# Sheet1.net
KiCad netlist of a schematic drawn in Altium Designer
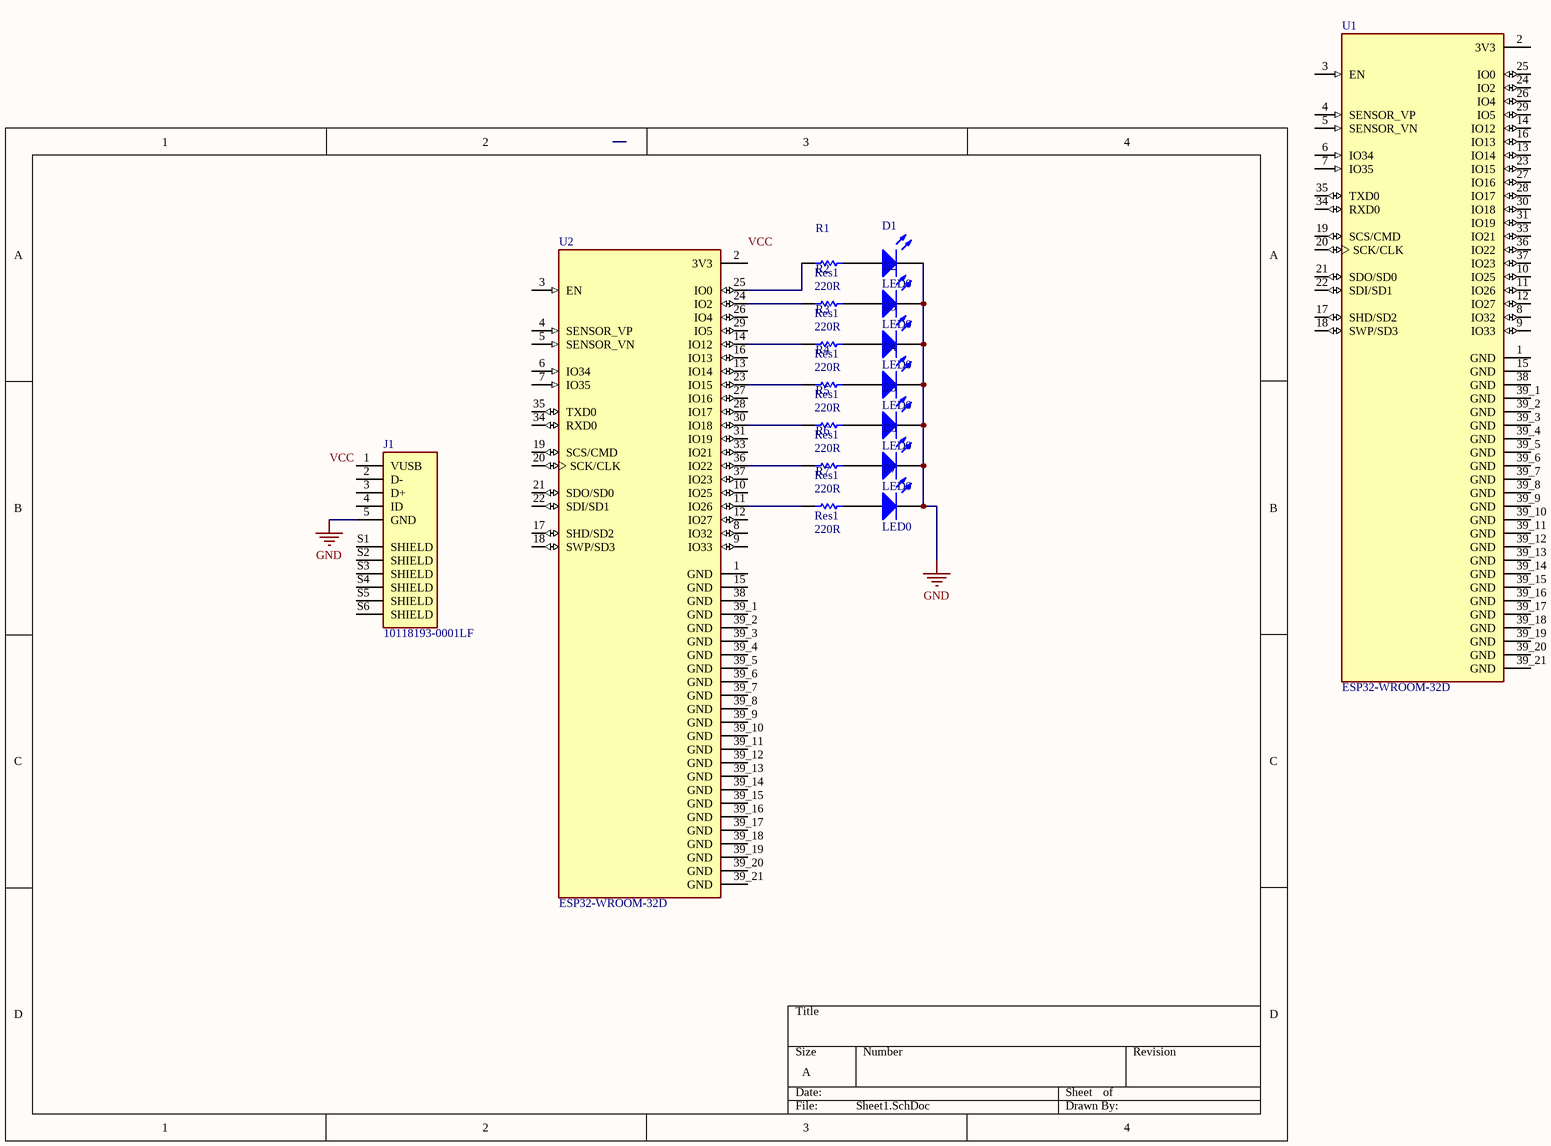
[diagram p0: Sheet1.SchDoc]

(export (version "E")
  (design (tool "Eeschema 10.0.6"))
  (components
    (comp (ref "D1")
      (value "LED0")
      (footprint "LED-0")
      (description "Typical INFRARED GaAs LED")
      (fields (field (name "PUBLISHER") "Altium Limited"))
      (libsource (lib "Miscellaneous Devices") (part "LED0"))
    )
    (comp (ref "D2")
      (value "LED0")
      (footprint "LED-0")
      (description "Typical INFRARED GaAs LED")
      (fields (field (name "PUBLISHER") "Altium Limited"))
      (libsource (lib "Miscellaneous Devices") (part "LED0"))
    )
    (comp (ref "D3")
      (value "LED0")
      (footprint "LED-0")
      (description "Typical INFRARED GaAs LED")
      (fields (field (name "PUBLISHER") "Altium Limited"))
      (libsource (lib "Miscellaneous Devices") (part "LED0"))
    )
    (comp (ref "D4")
      (value "LED0")
      (footprint "LED-0")
      (description "Typical INFRARED GaAs LED")
      (fields (field (name "PUBLISHER") "Altium Limited"))
      (libsource (lib "Miscellaneous Devices") (part "LED0"))
    )
    (comp (ref "D5")
      (value "LED0")
      (footprint "LED-0")
      (description "Typical INFRARED GaAs LED")
      (fields (field (name "PUBLISHER") "Altium Limited"))
      (libsource (lib "Miscellaneous Devices") (part "LED0"))
    )
    (comp (ref "D6")
      (value "LED0")
      (footprint "LED-0")
      (description "Typical INFRARED GaAs LED")
      (fields (field (name "PUBLISHER") "Altium Limited"))
      (libsource (lib "Miscellaneous Devices") (part "LED0"))
    )
    (comp (ref "D7")
      (value "LED0")
      (footprint "LED-0")
      (description "Typical INFRARED GaAs LED")
      (fields (field (name "PUBLISHER") "Altium Limited"))
      (libsource (lib "Miscellaneous Devices") (part "LED0"))
    )
    (comp (ref "J1")
      (value "10118193-0001LF")
      (footprint "AMPHENOL_10118193-0001LF")
      (description "Micro USB 2.0, Input Output Connectors, B TYPE RECEPTACLE")
      (fields (field (name "MF") "Amphenol ICC"))
      (libsource (lib "10118193-0001LF") (part "10118193-0001LF"))
    )
    (comp (ref "R1")
      (value "Res1")
      (footprint "AXIAL-0.3")
      (description "Resistor")
      (fields (field (name "ALTIUM_VALUE") "220R") (field (name "PUBLISHER") "Altium Limited"))
      (libsource (lib "Miscellaneous Devices") (part "Res1"))
    )
    (comp (ref "R2")
      (value "Res1")
      (footprint "AXIAL-0.3")
      (description "Resistor")
      (fields (field (name "ALTIUM_VALUE") "220R") (field (name "PUBLISHER") "Altium Limited"))
      (libsource (lib "Miscellaneous Devices") (part "Res1"))
    )
    (comp (ref "R3")
      (value "Res1")
      (footprint "AXIAL-0.3")
      (description "Resistor")
      (fields (field (name "ALTIUM_VALUE") "220R") (field (name "PUBLISHER") "Altium Limited"))
      (libsource (lib "Miscellaneous Devices") (part "Res1"))
    )
    (comp (ref "R4")
      (value "Res1")
      (footprint "AXIAL-0.3")
      (description "Resistor")
      (fields (field (name "ALTIUM_VALUE") "220R") (field (name "PUBLISHER") "Altium Limited"))
      (libsource (lib "Miscellaneous Devices") (part "Res1"))
    )
    (comp (ref "R5")
      (value "Res1")
      (footprint "AXIAL-0.3")
      (description "Resistor")
      (fields (field (name "ALTIUM_VALUE") "220R") (field (name "PUBLISHER") "Altium Limited"))
      (libsource (lib "Miscellaneous Devices") (part "Res1"))
    )
    (comp (ref "R6")
      (value "Res1")
      (footprint "AXIAL-0.3")
      (description "Resistor")
      (fields (field (name "ALTIUM_VALUE") "220R") (field (name "PUBLISHER") "Altium Limited"))
      (libsource (lib "Miscellaneous Devices") (part "Res1"))
    )
    (comp (ref "R7")
      (value "Res1")
      (footprint "AXIAL-0.3")
      (description "Resistor")
      (fields (field (name "ALTIUM_VALUE") "220R") (field (name "PUBLISHER") "Altium Limited"))
      (libsource (lib "Miscellaneous Devices") (part "Res1"))
    )
    (comp (ref "U1")
      (value "ESP32-WROOM-32D")
      (footprint "MODULE_ESP32-WROOM-32D")
      (fields (field (name "MF") "Espressif Systems"))
      (libsource (lib "ESP32-WROOM-32D") (part "ESP32-WROOM-32D"))
    )
    (comp (ref "U2")
      (value "ESP32-WROOM-32D")
      (footprint "MODULE_ESP32-WROOM-32D")
      (fields (field (name "MF") "Espressif Systems"))
      (libsource (lib "ESP32-WROOM-32D") (part "ESP32-WROOM-32D"))
    )
  )
  (nets
    (net (code "2") (name "GND") (class "Default")
      (node (ref "D1") (pin "2") (pinfunction "K_2") (pintype "passive"))
      (node (ref "D2") (pin "2") (pinfunction "K_2") (pintype "passive"))
      (node (ref "D3") (pin "2") (pinfunction "K_2") (pintype "passive"))
      (node (ref "D4") (pin "2") (pinfunction "K_2") (pintype "passive"))
      (node (ref "D5") (pin "2") (pinfunction "K_2") (pintype "passive"))
      (node (ref "D6") (pin "2") (pinfunction "K_2") (pintype "passive"))
      (node (ref "D7") (pin "2") (pinfunction "K_2") (pintype "passive"))
      (node (ref "J1") (pin "5") (pinfunction "GND_5") (pintype "passive"))
    )
    (net (code "3") (name "Net-(D1-A)") (class "Default")
      (node (ref "D1") (pin "1") (pinfunction "A_1") (pintype "passive"))
      (node (ref "R1") (pin "2") (pinfunction "2_2") (pintype "passive"))
    )
    (net (code "4") (name "Net-(D2-A)") (class "Default")
      (node (ref "D2") (pin "1") (pinfunction "A_1") (pintype "passive"))
      (node (ref "R2") (pin "2") (pinfunction "2_2") (pintype "passive"))
    )
    (net (code "5") (name "Net-(D3-A)") (class "Default")
      (node (ref "D3") (pin "1") (pinfunction "A_1") (pintype "passive"))
      (node (ref "R3") (pin "2") (pinfunction "2_2") (pintype "passive"))
    )
    (net (code "6") (name "Net-(D4-A)") (class "Default")
      (node (ref "D4") (pin "1") (pinfunction "A_1") (pintype "passive"))
      (node (ref "R4") (pin "2") (pinfunction "2_2") (pintype "passive"))
    )
    (net (code "7") (name "Net-(D5-A)") (class "Default")
      (node (ref "D5") (pin "1") (pinfunction "A_1") (pintype "passive"))
      (node (ref "R5") (pin "2") (pinfunction "2_2") (pintype "passive"))
    )
    (net (code "8") (name "Net-(D6-A)") (class "Default")
      (node (ref "D6") (pin "1") (pinfunction "A_1") (pintype "passive"))
      (node (ref "R6") (pin "2") (pinfunction "2_2") (pintype "passive"))
    )
    (net (code "9") (name "Net-(D7-A)") (class "Default")
      (node (ref "D7") (pin "1") (pinfunction "A_1") (pintype "passive"))
      (node (ref "R7") (pin "2") (pinfunction "2_2") (pintype "passive"))
    )
    (net (code "10") (name "Net-(U2-IO0)") (class "Default")
      (node (ref "R1") (pin "1") (pinfunction "1_1") (pintype "passive"))
      (node (ref "U2") (pin "25") (pinfunction "IO0_25") (pintype "bidirectional"))
    )
    (net (code "11") (name "Net-(U2-IO2)") (class "Default")
      (node (ref "R2") (pin "1") (pinfunction "1_1") (pintype "passive"))
      (node (ref "U2") (pin "24") (pinfunction "IO2_24") (pintype "bidirectional"))
    )
    (net (code "12") (name "Net-(U2-IO12)") (class "Default")
      (node (ref "R3") (pin "1") (pinfunction "1_1") (pintype "passive"))
      (node (ref "U2") (pin "14") (pinfunction "IO12_14") (pintype "bidirectional"))
    )
    (net (code "13") (name "Net-(U2-IO15)") (class "Default")
      (node (ref "R4") (pin "1") (pinfunction "1_1") (pintype "passive"))
      (node (ref "U2") (pin "23") (pinfunction "IO15_23") (pintype "bidirectional"))
    )
    (net (code "14") (name "Net-(U2-IO18)") (class "Default")
      (node (ref "R5") (pin "1") (pinfunction "1_1") (pintype "passive"))
      (node (ref "U2") (pin "30") (pinfunction "IO18_30") (pintype "bidirectional"))
    )
    (net (code "15") (name "Net-(U2-IO22)") (class "Default")
      (node (ref "R6") (pin "1") (pinfunction "1_1") (pintype "passive"))
      (node (ref "U2") (pin "36") (pinfunction "IO22_36") (pintype "bidirectional"))
    )
    (net (code "16") (name "Net-(U2-IO26)") (class "Default")
      (node (ref "R7") (pin "1") (pinfunction "1_1") (pintype "passive"))
      (node (ref "U2") (pin "11") (pinfunction "IO26_11") (pintype "bidirectional"))
    )
    (net (code "17") (name "unconnected-(J1-D+-Pad3)") (class "Default")
      (node (ref "J1") (pin "3") (pinfunction "D+_3") (pintype "passive"))
    )
    (net (code "18") (name "unconnected-(J1-D--Pad2)") (class "Default")
      (node (ref "J1") (pin "2") (pinfunction "D-_2") (pintype "passive"))
    )
    (net (code "19") (name "unconnected-(J1-ID-Pad4)") (class "Default")
      (node (ref "J1") (pin "4") (pinfunction "ID_4") (pintype "passive"))
    )
    (net (code "20") (name "unconnected-(J1-SHIELD-PadS1)") (class "Default")
      (node (ref "J1") (pin "S1") (pinfunction "SHIELD_S1") (pintype "passive"))
    )
    (net (code "21") (name "unconnected-(J1-SHIELD-PadS2)") (class "Default")
      (node (ref "J1") (pin "S2") (pinfunction "SHIELD_S2") (pintype "passive"))
    )
    (net (code "22") (name "unconnected-(J1-SHIELD-PadS3)") (class "Default")
      (node (ref "J1") (pin "S3") (pinfunction "SHIELD_S3") (pintype "passive"))
    )
    (net (code "23") (name "unconnected-(J1-SHIELD-PadS4)") (class "Default")
      (node (ref "J1") (pin "S4") (pinfunction "SHIELD_S4") (pintype "passive"))
    )
    (net (code "24") (name "unconnected-(J1-SHIELD-PadS5)") (class "Default")
      (node (ref "J1") (pin "S5") (pinfunction "SHIELD_S5") (pintype "passive"))
    )
    (net (code "25") (name "unconnected-(J1-SHIELD-PadS6)") (class "Default")
      (node (ref "J1") (pin "S6") (pinfunction "SHIELD_S6") (pintype "passive"))
    )
    (net (code "26") (name "unconnected-(J1-VUSB-Pad1)") (class "Default")
      (node (ref "J1") (pin "1") (pinfunction "VUSB_1") (pintype "passive"))
    )
    (net (code "27") (name "unconnected-(U1-3V3-Pad2)") (class "Default")
      (node (ref "U1") (pin "2") (pinfunction "3V3_2") (pintype "power_in"))
    )
    (net (code "28") (name "unconnected-(U1-EN-Pad3)") (class "Default")
      (node (ref "U1") (pin "3") (pinfunction "EN_3") (pintype "input"))
    )
    (net (code "29") (name "unconnected-(U1-GND-Pad1)") (class "Default")
      (node (ref "U1") (pin "1") (pinfunction "GND_1") (pintype "power_in"))
    )
    (net (code "30") (name "unconnected-(U1-GND-Pad15)") (class "Default")
      (node (ref "U1") (pin "15") (pinfunction "GND_15") (pintype "power_in"))
    )
    (net (code "31") (name "unconnected-(U1-GND-Pad38)") (class "Default")
      (node (ref "U1") (pin "38") (pinfunction "GND_38") (pintype "power_in"))
    )
    (net (code "32") (name "unconnected-(U1-GND-Pad39_1)") (class "Default")
      (node (ref "U1") (pin "39_1") (pinfunction "GND_39_1") (pintype "power_in"))
    )
    (net (code "33") (name "unconnected-(U1-GND-Pad39_2)") (class "Default")
      (node (ref "U1") (pin "39_2") (pinfunction "GND_39_2") (pintype "power_in"))
    )
    (net (code "34") (name "unconnected-(U1-GND-Pad39_3)") (class "Default")
      (node (ref "U1") (pin "39_3") (pinfunction "GND_39_3") (pintype "power_in"))
    )
    (net (code "35") (name "unconnected-(U1-GND-Pad39_4)") (class "Default")
      (node (ref "U1") (pin "39_4") (pinfunction "GND_39_4") (pintype "power_in"))
    )
    (net (code "36") (name "unconnected-(U1-GND-Pad39_5)") (class "Default")
      (node (ref "U1") (pin "39_5") (pinfunction "GND_39_5") (pintype "power_in"))
    )
    (net (code "37") (name "unconnected-(U1-GND-Pad39_6)") (class "Default")
      (node (ref "U1") (pin "39_6") (pinfunction "GND_39_6") (pintype "power_in"))
    )
    (net (code "38") (name "unconnected-(U1-GND-Pad39_7)") (class "Default")
      (node (ref "U1") (pin "39_7") (pinfunction "GND_39_7") (pintype "power_in"))
    )
    (net (code "39") (name "unconnected-(U1-GND-Pad39_8)") (class "Default")
      (node (ref "U1") (pin "39_8") (pinfunction "GND_39_8") (pintype "power_in"))
    )
    (net (code "40") (name "unconnected-(U1-GND-Pad39_9)") (class "Default")
      (node (ref "U1") (pin "39_9") (pinfunction "GND_39_9") (pintype "power_in"))
    )
    (net (code "41") (name "unconnected-(U1-GND-Pad39_10)") (class "Default")
      (node (ref "U1") (pin "39_10") (pinfunction "GND_39_10") (pintype "power_in"))
    )
    (net (code "42") (name "unconnected-(U1-GND-Pad39_11)") (class "Default")
      (node (ref "U1") (pin "39_11") (pinfunction "GND_39_11") (pintype "power_in"))
    )
    (net (code "43") (name "unconnected-(U1-GND-Pad39_12)") (class "Default")
      (node (ref "U1") (pin "39_12") (pinfunction "GND_39_12") (pintype "power_in"))
    )
    (net (code "44") (name "unconnected-(U1-GND-Pad39_13)") (class "Default")
      (node (ref "U1") (pin "39_13") (pinfunction "GND_39_13") (pintype "power_in"))
    )
    (net (code "45") (name "unconnected-(U1-GND-Pad39_14)") (class "Default")
      (node (ref "U1") (pin "39_14") (pinfunction "GND_39_14") (pintype "power_in"))
    )
    (net (code "46") (name "unconnected-(U1-GND-Pad39_15)") (class "Default")
      (node (ref "U1") (pin "39_15") (pinfunction "GND_39_15") (pintype "power_in"))
    )
    (net (code "47") (name "unconnected-(U1-GND-Pad39_16)") (class "Default")
      (node (ref "U1") (pin "39_16") (pinfunction "GND_39_16") (pintype "power_in"))
    )
    (net (code "48") (name "unconnected-(U1-GND-Pad39_17)") (class "Default")
      (node (ref "U1") (pin "39_17") (pinfunction "GND_39_17") (pintype "power_in"))
    )
    (net (code "49") (name "unconnected-(U1-GND-Pad39_18)") (class "Default")
      (node (ref "U1") (pin "39_18") (pinfunction "GND_39_18") (pintype "power_in"))
    )
    (net (code "50") (name "unconnected-(U1-GND-Pad39_19)") (class "Default")
      (node (ref "U1") (pin "39_19") (pinfunction "GND_39_19") (pintype "power_in"))
    )
    (net (code "51") (name "unconnected-(U1-GND-Pad39_20)") (class "Default")
      (node (ref "U1") (pin "39_20") (pinfunction "GND_39_20") (pintype "power_in"))
    )
    (net (code "52") (name "unconnected-(U1-GND-Pad39_21)") (class "Default")
      (node (ref "U1") (pin "39_21") (pinfunction "GND_39_21") (pintype "power_in"))
    )
    (net (code "53") (name "unconnected-(U1-IO0-Pad25)") (class "Default")
      (node (ref "U1") (pin "25") (pinfunction "IO0_25") (pintype "bidirectional"))
    )
    (net (code "54") (name "unconnected-(U1-IO2-Pad24)") (class "Default")
      (node (ref "U1") (pin "24") (pinfunction "IO2_24") (pintype "bidirectional"))
    )
    (net (code "55") (name "unconnected-(U1-IO4-Pad26)") (class "Default")
      (node (ref "U1") (pin "26") (pinfunction "IO4_26") (pintype "bidirectional"))
    )
    (net (code "56") (name "unconnected-(U1-IO5-Pad29)") (class "Default")
      (node (ref "U1") (pin "29") (pinfunction "IO5_29") (pintype "bidirectional"))
    )
    (net (code "57") (name "unconnected-(U1-IO12-Pad14)") (class "Default")
      (node (ref "U1") (pin "14") (pinfunction "IO12_14") (pintype "bidirectional"))
    )
    (net (code "58") (name "unconnected-(U1-IO13-Pad16)") (class "Default")
      (node (ref "U1") (pin "16") (pinfunction "IO13_16") (pintype "bidirectional"))
    )
    (net (code "59") (name "unconnected-(U1-IO14-Pad13)") (class "Default")
      (node (ref "U1") (pin "13") (pinfunction "IO14_13") (pintype "bidirectional"))
    )
    (net (code "60") (name "unconnected-(U1-IO15-Pad23)") (class "Default")
      (node (ref "U1") (pin "23") (pinfunction "IO15_23") (pintype "bidirectional"))
    )
    (net (code "61") (name "unconnected-(U1-IO16-Pad27)") (class "Default")
      (node (ref "U1") (pin "27") (pinfunction "IO16_27") (pintype "bidirectional"))
    )
    (net (code "62") (name "unconnected-(U1-IO17-Pad28)") (class "Default")
      (node (ref "U1") (pin "28") (pinfunction "IO17_28") (pintype "bidirectional"))
    )
    (net (code "63") (name "unconnected-(U1-IO18-Pad30)") (class "Default")
      (node (ref "U1") (pin "30") (pinfunction "IO18_30") (pintype "bidirectional"))
    )
    (net (code "64") (name "unconnected-(U1-IO19-Pad31)") (class "Default")
      (node (ref "U1") (pin "31") (pinfunction "IO19_31") (pintype "bidirectional"))
    )
    (net (code "65") (name "unconnected-(U1-IO21-Pad33)") (class "Default")
      (node (ref "U1") (pin "33") (pinfunction "IO21_33") (pintype "bidirectional"))
    )
    (net (code "66") (name "unconnected-(U1-IO22-Pad36)") (class "Default")
      (node (ref "U1") (pin "36") (pinfunction "IO22_36") (pintype "bidirectional"))
    )
    (net (code "67") (name "unconnected-(U1-IO23-Pad37)") (class "Default")
      (node (ref "U1") (pin "37") (pinfunction "IO23_37") (pintype "bidirectional"))
    )
    (net (code "68") (name "unconnected-(U1-IO25-Pad10)") (class "Default")
      (node (ref "U1") (pin "10") (pinfunction "IO25_10") (pintype "bidirectional"))
    )
    (net (code "69") (name "unconnected-(U1-IO26-Pad11)") (class "Default")
      (node (ref "U1") (pin "11") (pinfunction "IO26_11") (pintype "bidirectional"))
    )
    (net (code "70") (name "unconnected-(U1-IO27-Pad12)") (class "Default")
      (node (ref "U1") (pin "12") (pinfunction "IO27_12") (pintype "bidirectional"))
    )
    (net (code "71") (name "unconnected-(U1-IO32-Pad8)") (class "Default")
      (node (ref "U1") (pin "8") (pinfunction "IO32_8") (pintype "bidirectional"))
    )
    (net (code "72") (name "unconnected-(U1-IO33-Pad9)") (class "Default")
      (node (ref "U1") (pin "9") (pinfunction "IO33_9") (pintype "bidirectional"))
    )
    (net (code "73") (name "unconnected-(U1-IO34-Pad6)") (class "Default")
      (node (ref "U1") (pin "6") (pinfunction "IO34_6") (pintype "input"))
    )
    (net (code "74") (name "unconnected-(U1-IO35-Pad7)") (class "Default")
      (node (ref "U1") (pin "7") (pinfunction "IO35_7") (pintype "input"))
    )
    (net (code "75") (name "unconnected-(U1-RXD0-Pad34)") (class "Default")
      (node (ref "U1") (pin "34") (pinfunction "RXD0_34") (pintype "bidirectional"))
    )
    (net (code "76") (name "unconnected-(U1-SCK{slash}CLK-Pad20)") (class "Default")
      (node (ref "U1") (pin "20") (pinfunction "SCK/CLK_20") (pintype "bidirectional"))
    )
    (net (code "77") (name "unconnected-(U1-SCS{slash}CMD-Pad19)") (class "Default")
      (node (ref "U1") (pin "19") (pinfunction "SCS/CMD_19") (pintype "bidirectional"))
    )
    (net (code "78") (name "unconnected-(U1-SDI{slash}SD1-Pad22)") (class "Default")
      (node (ref "U1") (pin "22") (pinfunction "SDI/SD1_22") (pintype "bidirectional"))
    )
    (net (code "79") (name "unconnected-(U1-SDO{slash}SD0-Pad21)") (class "Default")
      (node (ref "U1") (pin "21") (pinfunction "SDO/SD0_21") (pintype "bidirectional"))
    )
    (net (code "80") (name "unconnected-(U1-SENSOR_VN-Pad5)") (class "Default")
      (node (ref "U1") (pin "5") (pinfunction "SENSOR_VN_5") (pintype "input"))
    )
    (net (code "81") (name "unconnected-(U1-SENSOR_VP-Pad4)") (class "Default")
      (node (ref "U1") (pin "4") (pinfunction "SENSOR_VP_4") (pintype "input"))
    )
    (net (code "82") (name "unconnected-(U1-SHD{slash}SD2-Pad17)") (class "Default")
      (node (ref "U1") (pin "17") (pinfunction "SHD/SD2_17") (pintype "bidirectional"))
    )
    (net (code "83") (name "unconnected-(U1-SWP{slash}SD3-Pad18)") (class "Default")
      (node (ref "U1") (pin "18") (pinfunction "SWP/SD3_18") (pintype "bidirectional"))
    )
    (net (code "84") (name "unconnected-(U1-TXD0-Pad35)") (class "Default")
      (node (ref "U1") (pin "35") (pinfunction "TXD0_35") (pintype "bidirectional"))
    )
    (net (code "85") (name "unconnected-(U2-3V3-Pad2)") (class "Default")
      (node (ref "U2") (pin "2") (pinfunction "3V3_2") (pintype "power_in"))
    )
    (net (code "86") (name "unconnected-(U2-EN-Pad3)") (class "Default")
      (node (ref "U2") (pin "3") (pinfunction "EN_3") (pintype "input"))
    )
    (net (code "87") (name "unconnected-(U2-GND-Pad1)") (class "Default")
      (node (ref "U2") (pin "1") (pinfunction "GND_1") (pintype "power_in"))
    )
    (net (code "88") (name "unconnected-(U2-GND-Pad15)") (class "Default")
      (node (ref "U2") (pin "15") (pinfunction "GND_15") (pintype "power_in"))
    )
    (net (code "89") (name "unconnected-(U2-GND-Pad38)") (class "Default")
      (node (ref "U2") (pin "38") (pinfunction "GND_38") (pintype "power_in"))
    )
    (net (code "90") (name "unconnected-(U2-GND-Pad39_1)") (class "Default")
      (node (ref "U2") (pin "39_1") (pinfunction "GND_39_1") (pintype "power_in"))
    )
    (net (code "91") (name "unconnected-(U2-GND-Pad39_2)") (class "Default")
      (node (ref "U2") (pin "39_2") (pinfunction "GND_39_2") (pintype "power_in"))
    )
    (net (code "92") (name "unconnected-(U2-GND-Pad39_3)") (class "Default")
      (node (ref "U2") (pin "39_3") (pinfunction "GND_39_3") (pintype "power_in"))
    )
    (net (code "93") (name "unconnected-(U2-GND-Pad39_4)") (class "Default")
      (node (ref "U2") (pin "39_4") (pinfunction "GND_39_4") (pintype "power_in"))
    )
    (net (code "94") (name "unconnected-(U2-GND-Pad39_5)") (class "Default")
      (node (ref "U2") (pin "39_5") (pinfunction "GND_39_5") (pintype "power_in"))
    )
    (net (code "95") (name "unconnected-(U2-GND-Pad39_6)") (class "Default")
      (node (ref "U2") (pin "39_6") (pinfunction "GND_39_6") (pintype "power_in"))
    )
    (net (code "96") (name "unconnected-(U2-GND-Pad39_7)") (class "Default")
      (node (ref "U2") (pin "39_7") (pinfunction "GND_39_7") (pintype "power_in"))
    )
    (net (code "97") (name "unconnected-(U2-GND-Pad39_8)") (class "Default")
      (node (ref "U2") (pin "39_8") (pinfunction "GND_39_8") (pintype "power_in"))
    )
    (net (code "98") (name "unconnected-(U2-GND-Pad39_9)") (class "Default")
      (node (ref "U2") (pin "39_9") (pinfunction "GND_39_9") (pintype "power_in"))
    )
    (net (code "99") (name "unconnected-(U2-GND-Pad39_10)") (class "Default")
      (node (ref "U2") (pin "39_10") (pinfunction "GND_39_10") (pintype "power_in"))
    )
    (net (code "100") (name "unconnected-(U2-GND-Pad39_11)") (class "Default")
      (node (ref "U2") (pin "39_11") (pinfunction "GND_39_11") (pintype "power_in"))
    )
    (net (code "101") (name "unconnected-(U2-GND-Pad39_12)") (class "Default")
      (node (ref "U2") (pin "39_12") (pinfunction "GND_39_12") (pintype "power_in"))
    )
    (net (code "102") (name "unconnected-(U2-GND-Pad39_13)") (class "Default")
      (node (ref "U2") (pin "39_13") (pinfunction "GND_39_13") (pintype "power_in"))
    )
    (net (code "103") (name "unconnected-(U2-GND-Pad39_14)") (class "Default")
      (node (ref "U2") (pin "39_14") (pinfunction "GND_39_14") (pintype "power_in"))
    )
    (net (code "104") (name "unconnected-(U2-GND-Pad39_15)") (class "Default")
      (node (ref "U2") (pin "39_15") (pinfunction "GND_39_15") (pintype "power_in"))
    )
    (net (code "105") (name "unconnected-(U2-GND-Pad39_16)") (class "Default")
      (node (ref "U2") (pin "39_16") (pinfunction "GND_39_16") (pintype "power_in"))
    )
    (net (code "106") (name "unconnected-(U2-GND-Pad39_17)") (class "Default")
      (node (ref "U2") (pin "39_17") (pinfunction "GND_39_17") (pintype "power_in"))
    )
    (net (code "107") (name "unconnected-(U2-GND-Pad39_18)") (class "Default")
      (node (ref "U2") (pin "39_18") (pinfunction "GND_39_18") (pintype "power_in"))
    )
    (net (code "108") (name "unconnected-(U2-GND-Pad39_19)") (class "Default")
      (node (ref "U2") (pin "39_19") (pinfunction "GND_39_19") (pintype "power_in"))
    )
    (net (code "109") (name "unconnected-(U2-GND-Pad39_20)") (class "Default")
      (node (ref "U2") (pin "39_20") (pinfunction "GND_39_20") (pintype "power_in"))
    )
    (net (code "110") (name "unconnected-(U2-GND-Pad39_21)") (class "Default")
      (node (ref "U2") (pin "39_21") (pinfunction "GND_39_21") (pintype "power_in"))
    )
    (net (code "111") (name "unconnected-(U2-IO4-Pad26)") (class "Default")
      (node (ref "U2") (pin "26") (pinfunction "IO4_26") (pintype "bidirectional"))
    )
    (net (code "112") (name "unconnected-(U2-IO5-Pad29)") (class "Default")
      (node (ref "U2") (pin "29") (pinfunction "IO5_29") (pintype "bidirectional"))
    )
    (net (code "113") (name "unconnected-(U2-IO13-Pad16)") (class "Default")
      (node (ref "U2") (pin "16") (pinfunction "IO13_16") (pintype "bidirectional"))
    )
    (net (code "114") (name "unconnected-(U2-IO14-Pad13)") (class "Default")
      (node (ref "U2") (pin "13") (pinfunction "IO14_13") (pintype "bidirectional"))
    )
    (net (code "115") (name "unconnected-(U2-IO16-Pad27)") (class "Default")
      (node (ref "U2") (pin "27") (pinfunction "IO16_27") (pintype "bidirectional"))
    )
    (net (code "116") (name "unconnected-(U2-IO17-Pad28)") (class "Default")
      (node (ref "U2") (pin "28") (pinfunction "IO17_28") (pintype "bidirectional"))
    )
    (net (code "117") (name "unconnected-(U2-IO19-Pad31)") (class "Default")
      (node (ref "U2") (pin "31") (pinfunction "IO19_31") (pintype "bidirectional"))
    )
    (net (code "118") (name "unconnected-(U2-IO21-Pad33)") (class "Default")
      (node (ref "U2") (pin "33") (pinfunction "IO21_33") (pintype "bidirectional"))
    )
    (net (code "119") (name "unconnected-(U2-IO23-Pad37)") (class "Default")
      (node (ref "U2") (pin "37") (pinfunction "IO23_37") (pintype "bidirectional"))
    )
    (net (code "120") (name "unconnected-(U2-IO25-Pad10)") (class "Default")
      (node (ref "U2") (pin "10") (pinfunction "IO25_10") (pintype "bidirectional"))
    )
    (net (code "121") (name "unconnected-(U2-IO27-Pad12)") (class "Default")
      (node (ref "U2") (pin "12") (pinfunction "IO27_12") (pintype "bidirectional"))
    )
    (net (code "122") (name "unconnected-(U2-IO32-Pad8)") (class "Default")
      (node (ref "U2") (pin "8") (pinfunction "IO32_8") (pintype "bidirectional"))
    )
    (net (code "123") (name "unconnected-(U2-IO33-Pad9)") (class "Default")
      (node (ref "U2") (pin "9") (pinfunction "IO33_9") (pintype "bidirectional"))
    )
    (net (code "124") (name "unconnected-(U2-IO34-Pad6)") (class "Default")
      (node (ref "U2") (pin "6") (pinfunction "IO34_6") (pintype "input"))
    )
    (net (code "125") (name "unconnected-(U2-IO35-Pad7)") (class "Default")
      (node (ref "U2") (pin "7") (pinfunction "IO35_7") (pintype "input"))
    )
    (net (code "126") (name "unconnected-(U2-RXD0-Pad34)") (class "Default")
      (node (ref "U2") (pin "34") (pinfunction "RXD0_34") (pintype "bidirectional"))
    )
    (net (code "127") (name "unconnected-(U2-SCK{slash}CLK-Pad20)") (class "Default")
      (node (ref "U2") (pin "20") (pinfunction "SCK/CLK_20") (pintype "bidirectional"))
    )
    (net (code "128") (name "unconnected-(U2-SCS{slash}CMD-Pad19)") (class "Default")
      (node (ref "U2") (pin "19") (pinfunction "SCS/CMD_19") (pintype "bidirectional"))
    )
    (net (code "129") (name "unconnected-(U2-SDI{slash}SD1-Pad22)") (class "Default")
      (node (ref "U2") (pin "22") (pinfunction "SDI/SD1_22") (pintype "bidirectional"))
    )
    (net (code "130") (name "unconnected-(U2-SDO{slash}SD0-Pad21)") (class "Default")
      (node (ref "U2") (pin "21") (pinfunction "SDO/SD0_21") (pintype "bidirectional"))
    )
    (net (code "131") (name "unconnected-(U2-SENSOR_VN-Pad5)") (class "Default")
      (node (ref "U2") (pin "5") (pinfunction "SENSOR_VN_5") (pintype "input"))
    )
    (net (code "132") (name "unconnected-(U2-SENSOR_VP-Pad4)") (class "Default")
      (node (ref "U2") (pin "4") (pinfunction "SENSOR_VP_4") (pintype "input"))
    )
    (net (code "133") (name "unconnected-(U2-SHD{slash}SD2-Pad17)") (class "Default")
      (node (ref "U2") (pin "17") (pinfunction "SHD/SD2_17") (pintype "bidirectional"))
    )
    (net (code "134") (name "unconnected-(U2-SWP{slash}SD3-Pad18)") (class "Default")
      (node (ref "U2") (pin "18") (pinfunction "SWP/SD3_18") (pintype "bidirectional"))
    )
    (net (code "135") (name "unconnected-(U2-TXD0-Pad35)") (class "Default")
      (node (ref "U2") (pin "35") (pinfunction "TXD0_35") (pintype "bidirectional"))
    )
  )
)
